# pyro18.net
KiCad netlist of a schematic drawn in EAGLE
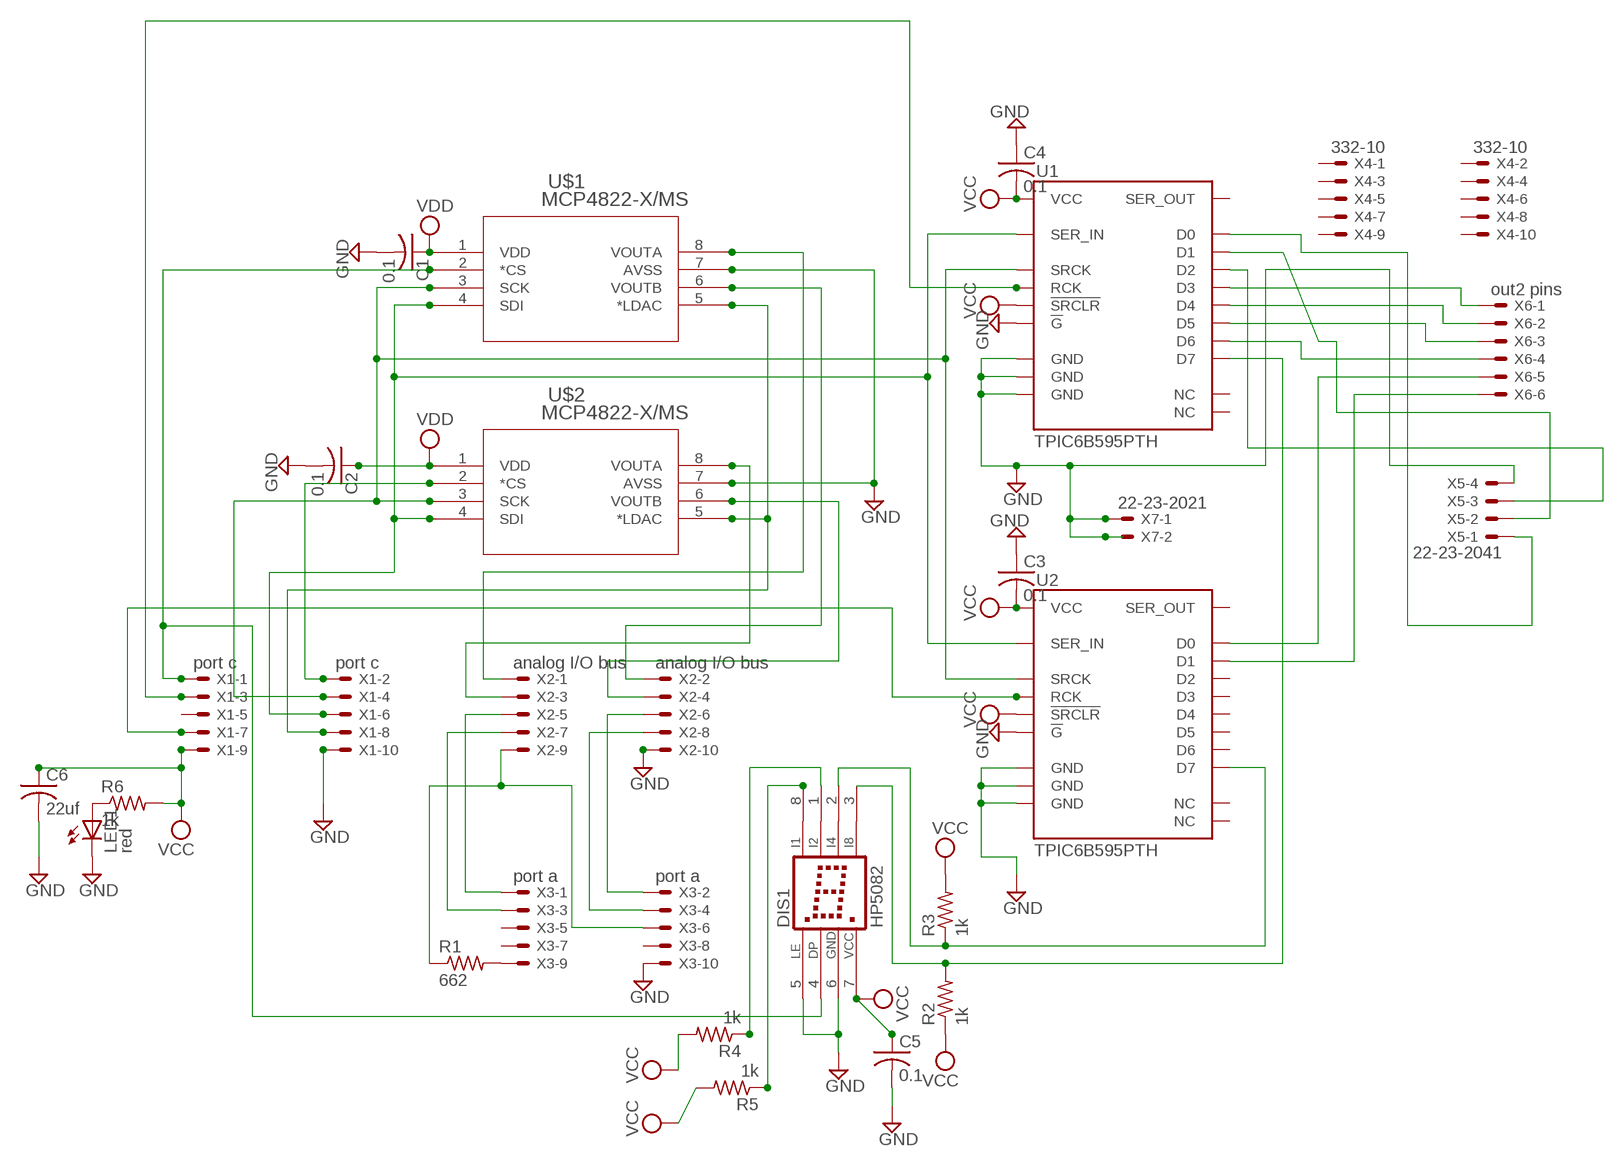
[diagram p0: schematic, sheet 1]

(export (version "E")
  (design (tool "Eeschema 10.0.6"))
  (components
    (comp (ref "C1")
      (value "0.1")
      (footprint "eagle-import:C0805")
      (libsource (lib "eagle-import") (part "C-USC0805"))
    )
    (comp (ref "C2")
      (value "0.1")
      (footprint "eagle-import:C0805")
      (libsource (lib "eagle-import") (part "C-USC0805"))
    )
    (comp (ref "C3")
      (value "0.1")
      (footprint "eagle-import:C0805")
      (libsource (lib "eagle-import") (part "C-USC0805"))
    )
    (comp (ref "C4")
      (value "0.1")
      (footprint "eagle-import:C0805")
      (libsource (lib "eagle-import") (part "C-USC0805"))
    )
    (comp (ref "C5")
      (value "0.1")
      (footprint "eagle-import:C0805")
      (libsource (lib "eagle-import") (part "C-USC0805"))
    )
    (comp (ref "C6")
      (value "22uf")
      (footprint "eagle-import:C0805")
      (libsource (lib "eagle-import") (part "C-USC0805"))
    )
    (comp (ref "DIS1")
      (value "HP5082")
      (footprint "eagle-import:HP5082")
      (libsource (lib "eagle-import") (part "HP5082"))
    )
    (comp (ref "LED1")
      (value "red")
      (footprint "eagle-import:LED3MM")
      (libsource (lib "eagle-import") (part "LED3MM"))
    )
    (comp (ref "R1")
      (value "662")
      (footprint "eagle-import:0207_2V")
      (libsource (lib "eagle-import") (part "R-US_0207/2V"))
    )
    (comp (ref "R2")
      (value "1k")
      (footprint "eagle-import:0207_2V")
      (libsource (lib "eagle-import") (part "R-US_0207/2V"))
    )
    (comp (ref "R3")
      (value "1k")
      (footprint "eagle-import:0207_2V")
      (libsource (lib "eagle-import") (part "R-US_0207/2V"))
    )
    (comp (ref "R4")
      (value "1k")
      (footprint "eagle-import:0207_2V")
      (libsource (lib "eagle-import") (part "R-US_0207/2V"))
    )
    (comp (ref "R5")
      (value "1k")
      (footprint "eagle-import:0207_2V")
      (libsource (lib "eagle-import") (part "R-US_0207/2V"))
    )
    (comp (ref "R6")
      (value "1k")
      (footprint "eagle-import:0207_2V")
      (libsource (lib "eagle-import") (part "R-US_0207/2V"))
    )
    (comp (ref "U$1")
      (value "MCP4822-X/MS")
      (footprint "eagle-import:MSOP8_MC")
      (libsource (lib "eagle-import") (part "MCP4822-X/MS"))
    )
    (comp (ref "U$2")
      (value "MCP4822-X/MS")
      (footprint "eagle-import:MSOP8_MC")
      (libsource (lib "eagle-import") (part "MCP4822-X/MS"))
    )
    (comp (ref "U1")
      (value "TPIC6B595PTH")
      (footprint "eagle-import:DIL20")
      (libsource (lib "eagle-import") (part "TPIC6B595PTH"))
    )
    (comp (ref "U2")
      (value "TPIC6B595PTH")
      (footprint "eagle-import:DIL20")
      (libsource (lib "eagle-import") (part "TPIC6B595PTH"))
    )
    (comp (ref "X1")
      (value "port c")
      (footprint "eagle-import:332-10")
      (libsource (lib "eagle-import") (part "332-10"))
    )
    (comp (ref "X2")
      (value "analog I/O bus")
      (footprint "eagle-import:332-10")
      (libsource (lib "eagle-import") (part "332-10"))
    )
    (comp (ref "X3")
      (value "port a")
      (footprint "eagle-import:332-10")
      (libsource (lib "eagle-import") (part "332-10"))
    )
    (comp (ref "X4")
      (value "332-10")
      (footprint "eagle-import:332-10")
      (libsource (lib "eagle-import") (part "332-10"))
    )
    (comp (ref "X5")
      (value "22-23-2041")
      (footprint "eagle-import:22-23-2041")
      (fields (field (name "MF") "MOLEX"))
      (libsource (lib "eagle-import") (part "22-23-2041"))
    )
    (comp (ref "X6")
      (value "out2 pins")
      (footprint "eagle-import:22-23-2061")
      (fields (field (name "MF") "MOLEX") (field (name "MPN") "22-23-2061"))
      (libsource (lib "eagle-import") (part "22-23-2061"))
    )
    (comp (ref "X7")
      (value "22-23-2021")
      (footprint "eagle-import:22-23-2021")
      (fields (field (name "MF") "MOLEX"))
      (libsource (lib "eagle-import") (part "22-23-2021"))
    )
  )
  (nets
    (net (code "1") (name "GND") (class "Default")
      (node (ref "C1") (pin "2") (pinfunction "2_2") (pintype "passive"))
      (node (ref "C2") (pin "2") (pinfunction "2_2") (pintype "passive"))
      (node (ref "C3") (pin "1") (pinfunction "1_1") (pintype "passive"))
      (node (ref "C4") (pin "1") (pinfunction "1_1") (pintype "passive"))
      (node (ref "C5") (pin "2") (pinfunction "2_2") (pintype "passive"))
      (node (ref "C6") (pin "2") (pinfunction "2_2") (pintype "passive"))
      (node (ref "DIS1") (pin "5") (pinfunction "LE_5") (pintype "input"))
      (node (ref "DIS1") (pin "6") (pinfunction "GND_6") (pintype "power_in"))
      (node (ref "LED1") (pin "K") (pinfunction "C_K") (pintype "passive"))
      (node (ref "U$1") (pin "7") (pinfunction "AVSS_7") (pintype "passive"))
      (node (ref "U$2") (pin "7") (pinfunction "AVSS_7") (pintype "passive"))
      (node (ref "U1") (pin "10") (pinfunction "GND_10") (pintype "power_in"))
      (node (ref "U1") (pin "11") (pinfunction "GND_11") (pintype "power_in"))
      (node (ref "U1") (pin "19") (pinfunction "GND_19") (pintype "power_in"))
      (node (ref "U1") (pin "9") (pinfunction "~{G}_9") (pintype "input"))
      (node (ref "U2") (pin "10") (pinfunction "GND_10") (pintype "power_in"))
      (node (ref "U2") (pin "11") (pinfunction "GND_11") (pintype "power_in"))
      (node (ref "U2") (pin "19") (pinfunction "GND_19") (pintype "power_in"))
      (node (ref "U2") (pin "9") (pinfunction "~{G}_9") (pintype "input"))
      (node (ref "X1") (pin "10") (pinfunction "S_10") (pintype "passive"))
      (node (ref "X2") (pin "10") (pinfunction "S_10") (pintype "passive"))
      (node (ref "X3") (pin "10") (pinfunction "S_10") (pintype "passive"))
      (node (ref "X5") (pin "4") (pinfunction "S_4") (pintype "passive"))
      (node (ref "X7") (pin "1") (pinfunction "S_1") (pintype "passive"))
      (node (ref "X7") (pin "2") (pinfunction "S_2") (pintype "passive"))
    )
    (net (code "2") (name "Net-(DIS1-DP)") (class "Default")
      (node (ref "DIS1") (pin "4") (pinfunction "DP_4") (pintype "input"))
      (node (ref "U$1") (pin "2") (pinfunction "*CS_2") (pintype "passive"))
      (node (ref "X1") (pin "1") (pinfunction "S_1") (pintype "passive"))
    )
    (net (code "3") (name "Net-(DIS1-I1)") (class "Default")
      (node (ref "DIS1") (pin "8") (pinfunction "I1_8") (pintype "input"))
      (node (ref "R5") (pin "1") (pinfunction "1_1") (pintype "passive"))
    )
    (net (code "4") (name "Net-(DIS1-I2)") (class "Default")
      (node (ref "DIS1") (pin "1") (pinfunction "I2_1") (pintype "input"))
      (node (ref "R4") (pin "1") (pinfunction "1_1") (pintype "passive"))
    )
    (net (code "5") (name "Net-(DIS1-I4)") (class "Default")
      (node (ref "DIS1") (pin "2") (pinfunction "I4_2") (pintype "input"))
      (node (ref "R3") (pin "1") (pinfunction "1_1") (pintype "passive"))
      (node (ref "U2") (pin "17") (pinfunction "D7_17") (pintype "output"))
    )
    (net (code "6") (name "Net-(DIS1-I8)") (class "Default")
      (node (ref "DIS1") (pin "3") (pinfunction "I8_3") (pintype "input"))
      (node (ref "R2") (pin "2") (pinfunction "2_2") (pintype "passive"))
      (node (ref "U1") (pin "17") (pinfunction "D7_17") (pintype "output"))
    )
    (net (code "7") (name "Net-(LED1-PadA)") (class "Default")
      (node (ref "LED1") (pin "A") (pinfunction "A_A") (pintype "passive"))
      (node (ref "R6") (pin "1") (pinfunction "1_1") (pintype "passive"))
    )
    (net (code "8") (name "Net-(U$1-*LDAC)") (class "Default")
      (node (ref "U$1") (pin "5") (pinfunction "*LDAC_5") (pintype "passive"))
      (node (ref "U$2") (pin "5") (pinfunction "*LDAC_5") (pintype "passive"))
      (node (ref "X1") (pin "8") (pinfunction "S_8") (pintype "passive"))
    )
    (net (code "9") (name "Net-(U$1-SCK)") (class "Default")
      (node (ref "U$1") (pin "3") (pinfunction "SCK_3") (pintype "passive"))
      (node (ref "U$2") (pin "3") (pinfunction "SCK_3") (pintype "passive"))
      (node (ref "U1") (pin "13") (pinfunction "SRCK_13") (pintype "input"))
      (node (ref "U2") (pin "13") (pinfunction "SRCK_13") (pintype "input"))
      (node (ref "X1") (pin "4") (pinfunction "S_4") (pintype "passive"))
    )
    (net (code "10") (name "Net-(U$1-SDI)") (class "Default")
      (node (ref "U$1") (pin "4") (pinfunction "SDI_4") (pintype "passive"))
      (node (ref "U$2") (pin "4") (pinfunction "SDI_4") (pintype "passive"))
      (node (ref "U1") (pin "3") (pinfunction "SER_IN_3") (pintype "input"))
      (node (ref "U2") (pin "3") (pinfunction "SER_IN_3") (pintype "input"))
      (node (ref "X1") (pin "6") (pinfunction "S_6") (pintype "passive"))
    )
    (net (code "11") (name "Net-(U$1-VOUTA)") (class "Default")
      (node (ref "U$1") (pin "8") (pinfunction "VOUTA_8") (pintype "passive"))
      (node (ref "X2") (pin "1") (pinfunction "S_1") (pintype "passive"))
    )
    (net (code "12") (name "Net-(U$1-VOUTB)") (class "Default")
      (node (ref "U$1") (pin "6") (pinfunction "VOUTB_6") (pintype "passive"))
      (node (ref "X2") (pin "2") (pinfunction "S_2") (pintype "passive"))
    )
    (net (code "13") (name "Net-(U$2-*CS)") (class "Default")
      (node (ref "U$2") (pin "2") (pinfunction "*CS_2") (pintype "passive"))
      (node (ref "X1") (pin "2") (pinfunction "S_2") (pintype "passive"))
    )
    (net (code "14") (name "Net-(U$2-VOUTA)") (class "Default")
      (node (ref "U$2") (pin "8") (pinfunction "VOUTA_8") (pintype "passive"))
      (node (ref "X2") (pin "3") (pinfunction "S_3") (pintype "passive"))
    )
    (net (code "15") (name "Net-(U$2-VOUTB)") (class "Default")
      (node (ref "U$2") (pin "6") (pinfunction "VOUTB_6") (pintype "passive"))
      (node (ref "X2") (pin "4") (pinfunction "S_4") (pintype "passive"))
    )
    (net (code "16") (name "Net-(U1-D0)") (class "Default")
      (node (ref "U1") (pin "4") (pinfunction "D0_4") (pintype "output"))
      (node (ref "X5") (pin "1") (pinfunction "S_1") (pintype "passive"))
    )
    (net (code "17") (name "Net-(U1-D1)") (class "Default")
      (node (ref "U1") (pin "5") (pinfunction "D1_5") (pintype "output"))
      (node (ref "X5") (pin "2") (pinfunction "S_2") (pintype "passive"))
    )
    (net (code "18") (name "Net-(U1-D2)") (class "Default")
      (node (ref "U1") (pin "6") (pinfunction "D2_6") (pintype "output"))
      (node (ref "X5") (pin "3") (pinfunction "S_3") (pintype "passive"))
    )
    (net (code "19") (name "Net-(U1-D3)") (class "Default")
      (node (ref "U1") (pin "7") (pinfunction "D3_7") (pintype "output"))
      (node (ref "X6") (pin "1") (pinfunction "S_1") (pintype "passive"))
    )
    (net (code "20") (name "Net-(U1-D4)") (class "Default")
      (node (ref "U1") (pin "14") (pinfunction "D4_14") (pintype "output"))
      (node (ref "X6") (pin "2") (pinfunction "S_2") (pintype "passive"))
    )
    (net (code "21") (name "Net-(U1-D5)") (class "Default")
      (node (ref "U1") (pin "15") (pinfunction "D5_15") (pintype "output"))
      (node (ref "X6") (pin "3") (pinfunction "S_3") (pintype "passive"))
    )
    (net (code "22") (name "Net-(U1-D6)") (class "Default")
      (node (ref "U1") (pin "16") (pinfunction "D6_16") (pintype "output"))
      (node (ref "X6") (pin "4") (pinfunction "S_4") (pintype "passive"))
    )
    (net (code "23") (name "Net-(U1-RCK)") (class "Default")
      (node (ref "U1") (pin "12") (pinfunction "RCK_12") (pintype "input"))
      (node (ref "X1") (pin "3") (pinfunction "S_3") (pintype "passive"))
    )
    (net (code "24") (name "Net-(U2-D0)") (class "Default")
      (node (ref "U2") (pin "4") (pinfunction "D0_4") (pintype "output"))
      (node (ref "X6") (pin "5") (pinfunction "S_5") (pintype "passive"))
    )
    (net (code "25") (name "Net-(U2-D1)") (class "Default")
      (node (ref "U2") (pin "5") (pinfunction "D1_5") (pintype "output"))
      (node (ref "X6") (pin "6") (pinfunction "S_6") (pintype "passive"))
    )
    (net (code "26") (name "Net-(U2-RCK)") (class "Default")
      (node (ref "U2") (pin "12") (pinfunction "RCK_12") (pintype "input"))
      (node (ref "X1") (pin "7") (pinfunction "S_7") (pintype "passive"))
    )
    (net (code "27") (name "Net-(X2F-S)") (class "Default")
      (node (ref "X2") (pin "5") (pinfunction "S_5") (pintype "passive"))
      (node (ref "X3") (pin "1") (pinfunction "S_1") (pintype "passive"))
    )
    (net (code "28") (name "Net-(X2G-S)") (class "Default")
      (node (ref "X2") (pin "6") (pinfunction "S_6") (pintype "passive"))
      (node (ref "X3") (pin "2") (pinfunction "S_2") (pintype "passive"))
    )
    (net (code "29") (name "Net-(X2H-S)") (class "Default")
      (node (ref "X2") (pin "7") (pinfunction "S_7") (pintype "passive"))
      (node (ref "X3") (pin "3") (pinfunction "S_3") (pintype "passive"))
    )
    (net (code "30") (name "Net-(X2I-S)") (class "Default")
      (node (ref "X2") (pin "8") (pinfunction "S_8") (pintype "passive"))
      (node (ref "X3") (pin "4") (pinfunction "S_4") (pintype "passive"))
    )
    (net (code "31") (name "Net-(X2J-S)") (class "Default")
      (node (ref "R1") (pin "1") (pinfunction "1_1") (pintype "passive"))
      (node (ref "X2") (pin "9") (pinfunction "S_9") (pintype "passive"))
      (node (ref "X3") (pin "6") (pinfunction "S_6") (pintype "passive"))
    )
    (net (code "32") (name "Net-(X3J-S)") (class "Default")
      (node (ref "R1") (pin "2") (pinfunction "2_2") (pintype "passive"))
      (node (ref "X3") (pin "9") (pinfunction "S_9") (pintype "passive"))
    )
    (net (code "33") (name "VCC") (class "Default")
      (node (ref "C3") (pin "2") (pinfunction "2_2") (pintype "passive"))
      (node (ref "C4") (pin "2") (pinfunction "2_2") (pintype "passive"))
      (node (ref "C5") (pin "1") (pinfunction "1_1") (pintype "passive"))
      (node (ref "C6") (pin "1") (pinfunction "1_1") (pintype "passive"))
      (node (ref "DIS1") (pin "7") (pinfunction "VCC_7") (pintype "power_in"))
      (node (ref "R2") (pin "1") (pinfunction "1_1") (pintype "passive"))
      (node (ref "R3") (pin "2") (pinfunction "2_2") (pintype "passive"))
      (node (ref "R4") (pin "2") (pinfunction "2_2") (pintype "passive"))
      (node (ref "R5") (pin "2") (pinfunction "2_2") (pintype "passive"))
      (node (ref "R6") (pin "2") (pinfunction "2_2") (pintype "passive"))
      (node (ref "U1") (pin "2") (pinfunction "VCC_2") (pintype "power_in"))
      (node (ref "U1") (pin "8") (pinfunction "~{SRCLR}_8") (pintype "input"))
      (node (ref "U2") (pin "2") (pinfunction "VCC_2") (pintype "power_in"))
      (node (ref "U2") (pin "8") (pinfunction "~{SRCLR}_8") (pintype "input"))
      (node (ref "X1") (pin "9") (pinfunction "S_9") (pintype "passive"))
    )
    (net (code "34") (name "VDD") (class "Default")
      (node (ref "C1") (pin "1") (pinfunction "1_1") (pintype "passive"))
      (node (ref "C2") (pin "1") (pinfunction "1_1") (pintype "passive"))
      (node (ref "U$1") (pin "1") (pinfunction "VDD_1") (pintype "passive"))
      (node (ref "U$2") (pin "1") (pinfunction "VDD_1") (pintype "passive"))
    )
    (net (code "35") (name "unconnected-(U1-NC-Pad1)") (class "Default")
      (node (ref "U1") (pin "1") (pinfunction "NC_1") (pintype "no_connect"))
    )
    (net (code "36") (name "unconnected-(U1-NC-Pad20)") (class "Default")
      (node (ref "U1") (pin "20") (pinfunction "NC_20") (pintype "no_connect"))
    )
    (net (code "37") (name "unconnected-(U1-SER_OUT-Pad18)") (class "Default")
      (node (ref "U1") (pin "18") (pinfunction "SER_OUT_18") (pintype "output"))
    )
    (net (code "38") (name "unconnected-(U2-D2-Pad6)") (class "Default")
      (node (ref "U2") (pin "6") (pinfunction "D2_6") (pintype "output"))
    )
    (net (code "39") (name "unconnected-(U2-D3-Pad7)") (class "Default")
      (node (ref "U2") (pin "7") (pinfunction "D3_7") (pintype "output"))
    )
    (net (code "40") (name "unconnected-(U2-D4-Pad14)") (class "Default")
      (node (ref "U2") (pin "14") (pinfunction "D4_14") (pintype "output"))
    )
    (net (code "41") (name "unconnected-(U2-D5-Pad15)") (class "Default")
      (node (ref "U2") (pin "15") (pinfunction "D5_15") (pintype "output"))
    )
    (net (code "42") (name "unconnected-(U2-D6-Pad16)") (class "Default")
      (node (ref "U2") (pin "16") (pinfunction "D6_16") (pintype "output"))
    )
    (net (code "43") (name "unconnected-(U2-NC-Pad1)") (class "Default")
      (node (ref "U2") (pin "1") (pinfunction "NC_1") (pintype "no_connect"))
    )
    (net (code "44") (name "unconnected-(U2-NC-Pad20)") (class "Default")
      (node (ref "U2") (pin "20") (pinfunction "NC_20") (pintype "no_connect"))
    )
    (net (code "45") (name "unconnected-(U2-SER_OUT-Pad18)") (class "Default")
      (node (ref "U2") (pin "18") (pinfunction "SER_OUT_18") (pintype "output"))
    )
    (net (code "46") (name "unconnected-(X1F-S-Pad5)") (class "Default")
      (node (ref "X1") (pin "5") (pinfunction "S_5") (pintype "passive"))
    )
    (net (code "47") (name "unconnected-(X3F-S-Pad5)") (class "Default")
      (node (ref "X3") (pin "5") (pinfunction "S_5") (pintype "passive"))
    )
    (net (code "48") (name "unconnected-(X3H-S-Pad7)") (class "Default")
      (node (ref "X3") (pin "7") (pinfunction "S_7") (pintype "passive"))
    )
    (net (code "49") (name "unconnected-(X3I-S-Pad8)") (class "Default")
      (node (ref "X3") (pin "8") (pinfunction "S_8") (pintype "passive"))
    )
    (net (code "50") (name "unconnected-(X4A-S-Pad1)") (class "Default")
      (node (ref "X4") (pin "1") (pinfunction "S_1") (pintype "passive"))
    )
    (net (code "51") (name "unconnected-(X4B-S-Pad10)") (class "Default")
      (node (ref "X4") (pin "10") (pinfunction "S_10") (pintype "passive"))
    )
    (net (code "52") (name "unconnected-(X4C-S-Pad2)") (class "Default")
      (node (ref "X4") (pin "2") (pinfunction "S_2") (pintype "passive"))
    )
    (net (code "53") (name "unconnected-(X4D-S-Pad3)") (class "Default")
      (node (ref "X4") (pin "3") (pinfunction "S_3") (pintype "passive"))
    )
    (net (code "54") (name "unconnected-(X4E-S-Pad4)") (class "Default")
      (node (ref "X4") (pin "4") (pinfunction "S_4") (pintype "passive"))
    )
    (net (code "55") (name "unconnected-(X4F-S-Pad5)") (class "Default")
      (node (ref "X4") (pin "5") (pinfunction "S_5") (pintype "passive"))
    )
    (net (code "56") (name "unconnected-(X4G-S-Pad6)") (class "Default")
      (node (ref "X4") (pin "6") (pinfunction "S_6") (pintype "passive"))
    )
    (net (code "57") (name "unconnected-(X4H-S-Pad7)") (class "Default")
      (node (ref "X4") (pin "7") (pinfunction "S_7") (pintype "passive"))
    )
    (net (code "58") (name "unconnected-(X4I-S-Pad8)") (class "Default")
      (node (ref "X4") (pin "8") (pinfunction "S_8") (pintype "passive"))
    )
    (net (code "59") (name "unconnected-(X4J-S-Pad9)") (class "Default")
      (node (ref "X4") (pin "9") (pinfunction "S_9") (pintype "passive"))
    )
  )
)
